# PROC051D_XDS110_Interface_1A.net
KiCad netlist of a schematic drawn in Altium Designer
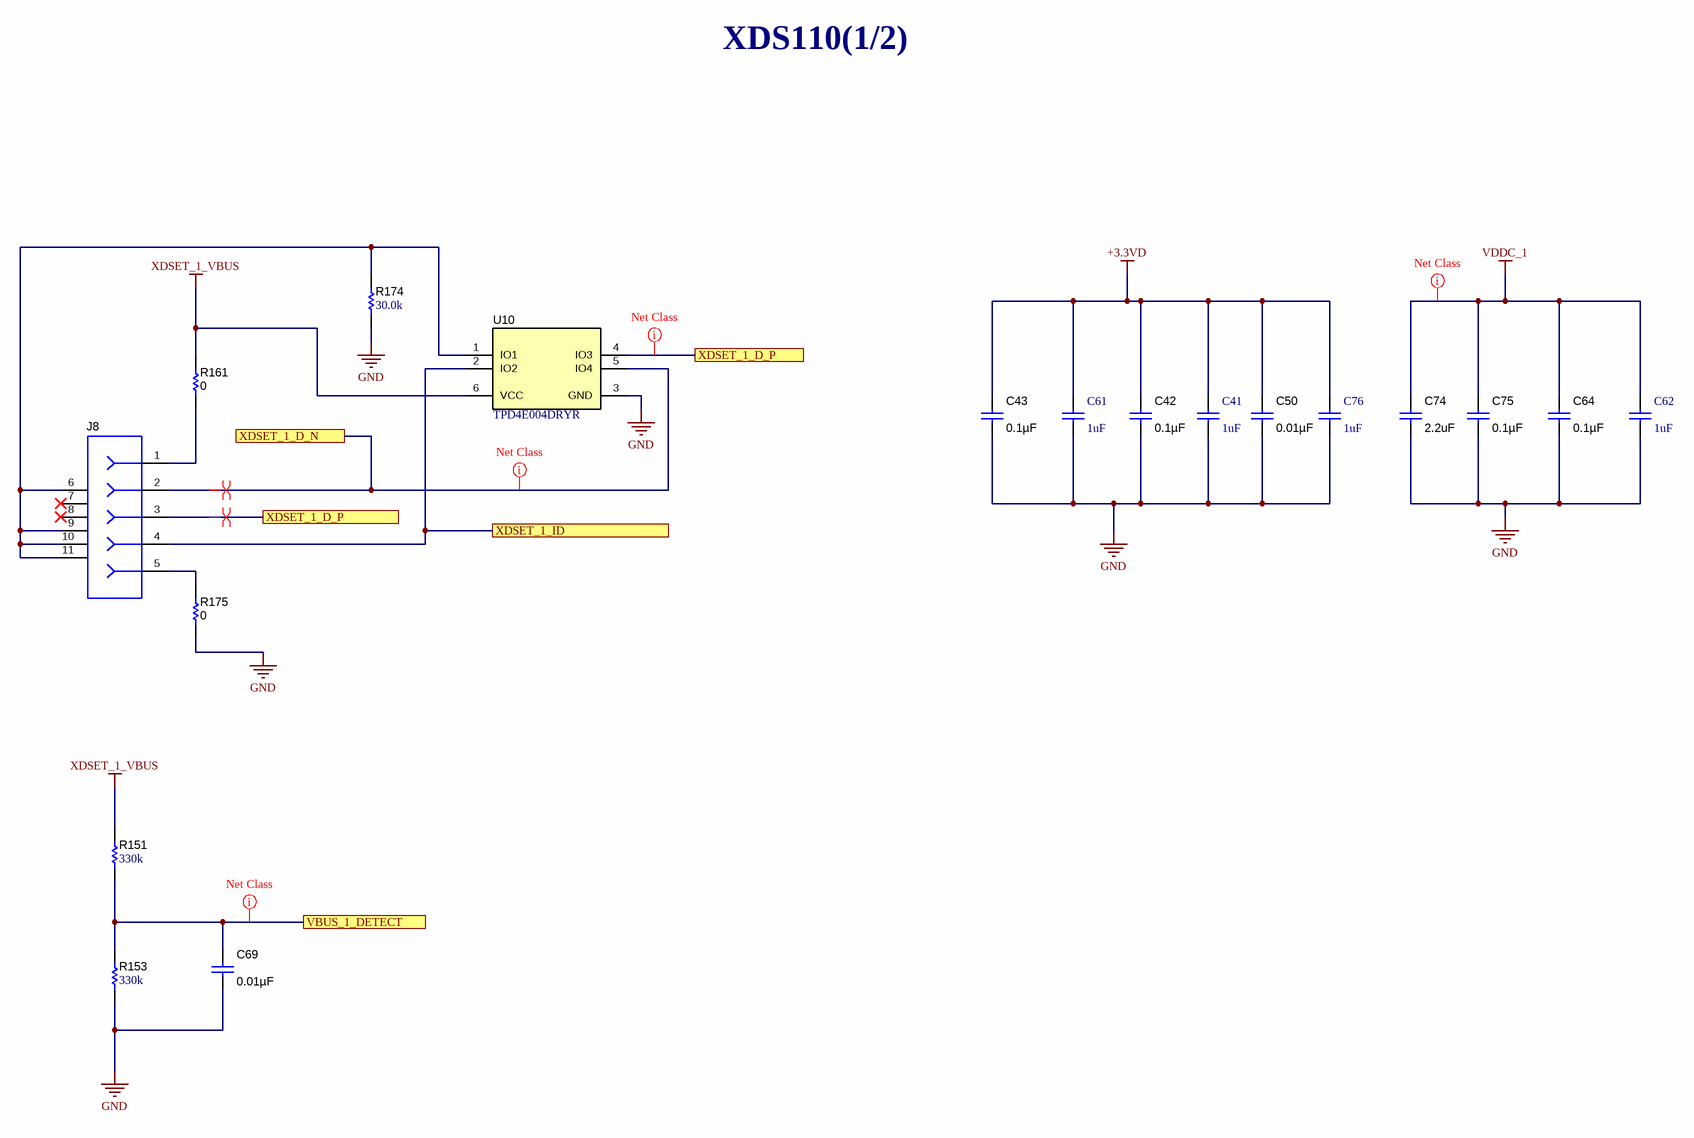
[diagram p0: PROC051D_XDS110 Interface_1A.SchDoc]

(export (version "E")
  (design (tool "Eeschema 10.0.6"))
  (components
    (comp (ref "C41")
      (value "GCM155C71A105KE38D")
      (footprint "0402_070")
      (description "CAP, CERM, 1 uF, 10 V, +/- 10%, X7S, AEC-Q200 Grade 1, 0402")
      (fields
        (field (name "MANUFACTURER") "MuRata")
        (field (name "VALUEDISPLAYED") "1uF")
        (field (name "PUBLISHER") "Texas Instruments")
      )
      (libsource (lib "Altium Vault - TI") (part "CMP-0006349-2"))
    )
    (comp (ref "C42")
      (value "C0402C104K8RACTU")
      (footprint "0402L")
      (description "CAP, CERM, 0.1 µF, 10 V,+/- 10%, X7R, 0402")
      (fields (field (name "MANUFACTURER") "Kemet") (field (name "VALUEDISPLAYED") "0.1µF"))
      (libsource (lib "Altium Vault - TI") (part "Capacitor"))
    )
    (comp (ref "C43")
      (value "C0402C104K8RACTU")
      (footprint "0402L")
      (description "CAP, CERM, 0.1 µF, 10 V,+/- 10%, X7R, 0402")
      (fields (field (name "MANUFACTURER") "Kemet") (field (name "VALUEDISPLAYED") "0.1µF"))
      (libsource (lib "Altium Vault - TI") (part "Capacitor"))
    )
    (comp (ref "C50")
      (value "C0402C103K4RACTU")
      (footprint "0402L")
      (description "CAP, CERM, 0.01 µF, 16 V,+/- 10%, X7R, 0402")
      (fields (field (name "MANUFACTURER") "Kemet") (field (name "VALUEDISPLAYED") "0.01µF"))
      (libsource (lib "Altium Vault - TI") (part "Capacitor"))
    )
    (comp (ref "C61")
      (value "GCM155C71A105KE38D")
      (footprint "0402_070")
      (description "CAP, CERM, 1 uF, 10 V, +/- 10%, X7S, AEC-Q200 Grade 1, 0402")
      (fields
        (field (name "MANUFACTURER") "MuRata")
        (field (name "VALUEDISPLAYED") "1uF")
        (field (name "PUBLISHER") "Texas Instruments")
      )
      (libsource (lib "Altium Vault - TI") (part "CMP-0006349-2"))
    )
    (comp (ref "C62")
      (value "GCM155C71A105KE38D")
      (footprint "0402_070")
      (description "CAP, CERM, 1 uF, 10 V, +/- 10%, X7S, AEC-Q200 Grade 1, 0402")
      (fields
        (field (name "MANUFACTURER") "MuRata")
        (field (name "VALUEDISPLAYED") "1uF")
        (field (name "PUBLISHER") "Texas Instruments")
      )
      (libsource (lib "Altium Vault - TI") (part "CMP-0006349-2"))
    )
    (comp (ref "C64")
      (value "C0402C104K8RACTU")
      (footprint "0402L")
      (description "CAP, CERM, 0.1 µF, 10 V,+/- 10%, X7R, 0402")
      (fields (field (name "MANUFACTURER") "Kemet") (field (name "VALUEDISPLAYED") "0.1µF"))
      (libsource (lib "Altium Vault - TI") (part "Capacitor"))
    )
    (comp (ref "C69")
      (value "C0402C103K4RACTU")
      (footprint "0402L")
      (description "CAP, CERM, 0.01 µF, 16 V,+/- 10%, X7R, 0402")
      (fields (field (name "MANUFACTURER") "Kemet") (field (name "VALUEDISPLAYED") "0.01µF"))
      (libsource (lib "Altium Vault - TI") (part "Capacitor"))
    )
    (comp (ref "C74")
      (value "C1005X7S1A225K050BC")
      (footprint "0402_065L")
      (description "CAP, CERM, 2.2 uF, 10 V, +/- 10%, X7S, 0402")
      (fields
        (field (name "MANUFACTURER") "TDK")
        (field (name "VALUEDISPLAYED") "2.2uF")
        (field (name "PUBLISHER") "Texas Instruments")
      )
      (libsource (lib "Altium Vault - TI") (part "CMP-0006302-2"))
    )
    (comp (ref "C75")
      (value "C0402C104K8RACTU")
      (footprint "0402L")
      (description "CAP, CERM, 0.1 µF, 10 V,+/- 10%, X7R, 0402")
      (fields (field (name "MANUFACTURER") "Kemet") (field (name "VALUEDISPLAYED") "0.1µF"))
      (libsource (lib "Altium Vault - TI") (part "Capacitor"))
    )
    (comp (ref "C76")
      (value "GCM155C71A105KE38D")
      (footprint "0402_070")
      (description "CAP, CERM, 1 uF, 10 V, +/- 10%, X7S, AEC-Q200 Grade 1, 0402")
      (fields
        (field (name "MANUFACTURER") "MuRata")
        (field (name "VALUEDISPLAYED") "1uF")
        (field (name "PUBLISHER") "Texas Instruments")
      )
      (libsource (lib "Altium Vault - TI") (part "CMP-0006349-2"))
    )
    (comp (ref "J8")
      (value "105017-0001")
      (footprint "CONN_105017-0001")
      (description "Connector, Receptacle, Micro-USB Type B, R/A, Bottom Mount SMT")
      (fields (field (name "MANUFACTURER") "Molex") (field (name "PUBLISHER") "Texas Instruments"))
      (libsource (lib "Altium Vault - TI") (part "CONN_105017-0001"))
    )
    (comp (ref "R151")
      (value "CRCW0402330KFKED")
      (footprint "0402L")
      (description "RES, 330 k, 1%, 0.063 W, AEC-Q200 Grade 0, 0402")
      (fields (field (name "MANUFACTURER") "Vishay-Dale") (field (name "VALUEDISPLAYED") "330k"))
      (libsource (lib "Altium Vault - TI") (part "Resistor"))
    )
    (comp (ref "R153")
      (value "CRCW0402330KFKED")
      (footprint "0402L")
      (description "RES, 330 k, 1%, 0.063 W, AEC-Q200 Grade 0, 0402")
      (fields (field (name "MANUFACTURER") "Vishay-Dale") (field (name "VALUEDISPLAYED") "330k"))
      (libsource (lib "Altium Vault - TI") (part "Resistor"))
    )
    (comp (ref "R161")
      (value "MCT06030Z0000ZP500")
      (footprint "0603")
      (description "RES, 0, 5%, 0.125 W, 0603")
      (fields
        (field (name "MANUFACTURER") "Vishay/Beyschlag")
        (field (name "VALUEDISPLAYED") "0")
        (field (name "PUBLISHER") "Texas Instruments")
      )
      (libsource (lib "Altium Vault - TI") (part "Resistor"))
    )
    (comp (ref "R174")
      (value "CRCW040230K0FKED")
      (footprint "0402L")
      (description "RES, 30.0 k, 1%, 0.063 W, AEC-Q200 Grade 0, 0402")
      (fields (field (name "MANUFACTURER") "Vishay-Dale") (field (name "VALUEDISPLAYED") "30.0k"))
      (libsource (lib "Altium Vault - TI") (part "Resistor"))
    )
    (comp (ref "R175")
      (value "MCT06030Z0000ZP500")
      (footprint "0603")
      (description "RES, 0, 5%, 0.125 W, 0603")
      (fields
        (field (name "MANUFACTURER") "Vishay/Beyschlag")
        (field (name "VALUEDISPLAYED") "0")
        (field (name "PUBLISHER") "Texas Instruments")
      )
      (libsource (lib "Altium Vault - TI") (part "Resistor"))
    )
    (comp (ref "U10")
      (value "TPD4E004DRYR")
      (footprint "DRY0006A")
      (description "4-Channel ESD Protection Array for High-Speed Data Interfaces, DRY0006A (USON-6)")
      (fields (field (name "MANUFACTURER") "Texas Instruments") (field (name "PARTNUMBER") "TPD4E004DRYR"))
      (libsource (lib "Altium Vault - TI") (part "TI-TPD4E004-SON_DRY-6"))
    )
  )
  (nets
    (net (code "1") (name "+3.3VD") (class "Default")
      (node (ref "C41") (pin "1") (pinfunction "1_1") (pintype "passive"))
      (node (ref "C42") (pin "2") (pinfunction "2_2") (pintype "passive"))
      (node (ref "C43") (pin "2") (pinfunction "2_2") (pintype "passive"))
      (node (ref "C50") (pin "2") (pinfunction "2_2") (pintype "passive"))
      (node (ref "C61") (pin "1") (pinfunction "1_1") (pintype "passive"))
      (node (ref "C76") (pin "1") (pinfunction "1_1") (pintype "passive"))
    )
    (net (code "2") (name "/VBUS_1_DETECT") (class "Default")
      (node (ref "C69") (pin "2") (pinfunction "2_2") (pintype "passive"))
      (node (ref "R151") (pin "1") (pinfunction "1_1") (pintype "passive"))
      (node (ref "R153") (pin "2") (pinfunction "2_2") (pintype "passive"))
    )
    (net (code "3") (name "/XDSET_1_D_N") (class "Default")
      (node (ref "J8") (pin "2") (pintype "passive"))
      (node (ref "U10") (pin "5") (pinfunction "IO4_5") (pintype "passive"))
    )
    (net (code "4") (name "/XDSET_1_D_P") (class "Default")
      (node (ref "J8") (pin "3") (pintype "passive"))
      (node (ref "U10") (pin "4") (pinfunction "IO3_4") (pintype "passive"))
    )
    (net (code "5") (name "/XDSET_1_ID") (class "Default")
      (node (ref "J8") (pin "4") (pintype "passive"))
      (node (ref "U10") (pin "2") (pinfunction "IO2_2") (pintype "passive"))
    )
    (net (code "6") (name "GND") (class "Default")
      (node (ref "C41") (pin "2") (pinfunction "2_2") (pintype "passive"))
      (node (ref "C42") (pin "1") (pinfunction "1_1") (pintype "passive"))
      (node (ref "C43") (pin "1") (pinfunction "1_1") (pintype "passive"))
      (node (ref "C50") (pin "1") (pinfunction "1_1") (pintype "passive"))
      (node (ref "C61") (pin "2") (pinfunction "2_2") (pintype "passive"))
      (node (ref "C62") (pin "2") (pinfunction "2_2") (pintype "passive"))
      (node (ref "C64") (pin "1") (pinfunction "1_1") (pintype "passive"))
      (node (ref "C69") (pin "1") (pinfunction "1_1") (pintype "passive"))
      (node (ref "C74") (pin "1") (pinfunction "1_1") (pintype "passive"))
      (node (ref "C75") (pin "1") (pinfunction "1_1") (pintype "passive"))
      (node (ref "C76") (pin "2") (pinfunction "2_2") (pintype "passive"))
      (node (ref "R153") (pin "1") (pinfunction "1_1") (pintype "passive"))
      (node (ref "R174") (pin "1") (pinfunction "1_1") (pintype "passive"))
      (node (ref "R175") (pin "1") (pinfunction "1_1") (pintype "passive"))
      (node (ref "U10") (pin "3") (pinfunction "GND_3") (pintype "power_in"))
    )
    (net (code "7") (name "Net-(J8-Pad1)") (class "Default")
      (node (ref "J8") (pin "1") (pintype "passive"))
      (node (ref "R161") (pin "1") (pinfunction "1_1") (pintype "passive"))
    )
    (net (code "8") (name "Net-(J8-Pad5)") (class "Default")
      (node (ref "J8") (pin "5") (pintype "passive"))
      (node (ref "R175") (pin "2") (pinfunction "2_2") (pintype "passive"))
    )
    (net (code "9") (name "Net-(U10-IO1)") (class "Default")
      (node (ref "J8") (pin "10") (pintype "passive"))
      (node (ref "J8") (pin "11") (pintype "passive"))
      (node (ref "J8") (pin "6") (pintype "passive"))
      (node (ref "J8") (pin "9") (pintype "passive"))
      (node (ref "R174") (pin "2") (pinfunction "2_2") (pintype "passive"))
      (node (ref "U10") (pin "1") (pinfunction "IO1_1") (pintype "passive"))
    )
    (net (code "10") (name "VDDC_1") (class "Default")
      (node (ref "C62") (pin "1") (pinfunction "1_1") (pintype "passive"))
      (node (ref "C64") (pin "2") (pinfunction "2_2") (pintype "passive"))
      (node (ref "C74") (pin "2") (pinfunction "2_2") (pintype "passive"))
      (node (ref "C75") (pin "2") (pinfunction "2_2") (pintype "passive"))
    )
    (net (code "11") (name "XDSET_1_VBUS") (class "Default")
      (node (ref "R151") (pin "2") (pinfunction "2_2") (pintype "passive"))
      (node (ref "R161") (pin "2") (pinfunction "2_2") (pintype "passive"))
      (node (ref "U10") (pin "6") (pinfunction "VCC_6") (pintype "power_in"))
    )
    (net (code "12") (name "unconnected-(J8-Pad7)") (class "Default")
      (node (ref "J8") (pin "7") (pintype "passive+no_connect"))
    )
    (net (code "13") (name "unconnected-(J8-Pad8)") (class "Default")
      (node (ref "J8") (pin "8") (pintype "passive+no_connect"))
    )
  )
)
